# SL_Config_2E.net
KiCad netlist of a schematic drawn in Altium Designer
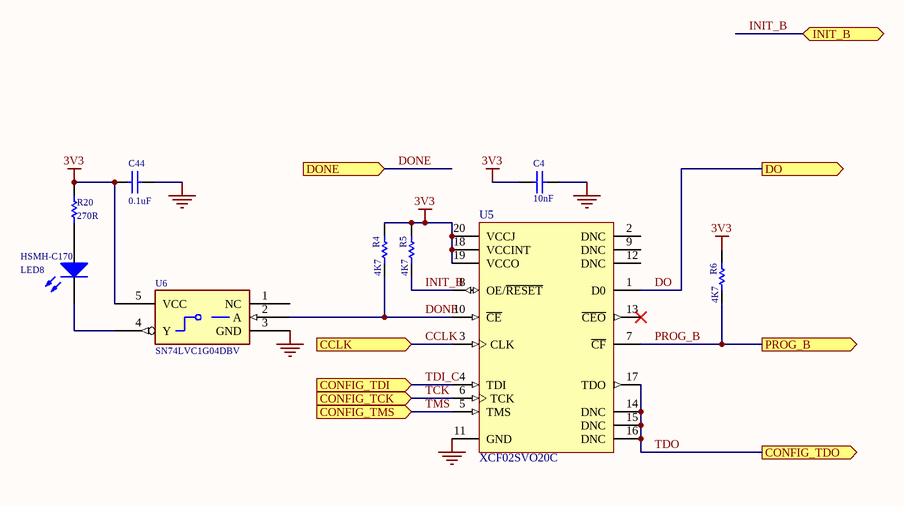
[diagram p0: SL_Config_2E.SchDoc]

(export (version "E")
  (design (tool "Eeschema 10.0.6"))
  (components
    (comp (ref "C4")
      (value "10nF")
      (footprint "CC1608-0603")
      (description "Capacitor")
      (libsource (lib "SpiritLevel_2E") (part "CAP"))
    )
    (comp (ref "C44")
      (value "0.1uF")
      (footprint "CC2012-0805")
      (description "Capacitor")
      (libsource (lib "SpiritLevel_2E") (part "CAP"))
    )
    (comp (ref "LED8")
      (value "HSMH-C170")
      (footprint "Spirit_Level_Project:SMD _LED")
      (description "Typical RED GaAs SMD LED Agilent make")
      (libsource (lib "SpiritLevel_2E") (part "HSMX-C670"))
    )
    (comp (ref "R4")
      (value "4K7")
      (footprint "Spirit_Level_Project:CR2012-0805")
      (description "Resistor")
      (libsource (lib "SpiritLevel_2E") (part "RES"))
    )
    (comp (ref "R5")
      (value "4K7")
      (footprint "Spirit_Level_Project:CR2012-0805")
      (description "Resistor")
      (libsource (lib "SpiritLevel_2E") (part "RES"))
    )
    (comp (ref "R6")
      (value "4K7")
      (footprint "Spirit_Level_Project:CR2012-0805")
      (description "Resistor")
      (libsource (lib "SpiritLevel_2E") (part "RES"))
    )
    (comp (ref "R20")
      (value "270R")
      (footprint "Spirit_Level_Project:CR2012-0805")
      (description "Resistor")
      (libsource (lib "SpiritLevel_2E") (part "RES"))
    )
    (comp (ref "U5")
      (value "XCF02SVO20C")
      (footprint "Spirit_Level_Project:VO20")
      (libsource (lib "SpiritLevel_2E") (part "XCF02SVO20C"))
    )
    (comp (ref "U6")
      (value "SN74LVC1G04DBV")
      (footprint "Spirit_Level_Project:SO-G5/P.95")
      (fields (field (name "MANUFACTURER") "TI"))
      (libsource (lib "SpiritLevel_2E") (part "SN74AHC1G04DBVR"))
    )
  )
  (nets
    (net (code "1") (name "/CCLK") (class "Default")
      (node (ref "U5") (pin "3") (pinfunction "CLK_3") (pintype "input"))
    )
    (net (code "2") (name "/DO") (class "Default")
      (node (ref "U5") (pin "1") (pinfunction "D0_1") (pintype "tri_state"))
    )
    (net (code "3") (name "/DONE") (class "Default")
      (node (ref "R4") (pin "2") (pinfunction "2_2") (pintype "passive"))
      (node (ref "U5") (pin "10") (pinfunction "~{CE}_10") (pintype "input"))
      (node (ref "U6") (pin "2") (pinfunction "A_2") (pintype "input"))
    )
    (net (code "4") (name "/INIT_B") (class "Default")
      (node (ref "R5") (pin "2") (pinfunction "2_2") (pintype "passive"))
      (node (ref "U5") (pin "8") (pinfunction "OE/~{RESET}_8") (pintype "bidirectional"))
    )
    (net (code "5") (name "/PROG_B") (class "Default")
      (node (ref "R6") (pin "2") (pinfunction "2_2") (pintype "passive"))
      (node (ref "U5") (pin "7") (pinfunction "~{CF}_7") (pintype "open_collector"))
    )
    (net (code "6") (name "/TCK") (class "Default")
      (node (ref "U5") (pin "6") (pinfunction "TCK_6") (pintype "input"))
    )
    (net (code "7") (name "/TDI_C") (class "Default")
      (node (ref "U5") (pin "4") (pinfunction "TDI_4") (pintype "input"))
    )
    (net (code "8") (name "/TDO") (class "Default")
      (node (ref "U5") (pin "14") (pinfunction "DNC_14") (pintype "passive"))
      (node (ref "U5") (pin "15") (pinfunction "DNC_15") (pintype "passive"))
      (node (ref "U5") (pin "16") (pinfunction "DNC_16") (pintype "passive"))
      (node (ref "U5") (pin "17") (pinfunction "TDO_17") (pintype "output"))
    )
    (net (code "9") (name "/TMS") (class "Default")
      (node (ref "U5") (pin "5") (pinfunction "TMS_5") (pintype "input"))
    )
    (net (code "10") (name "3V3") (class "Default")
      (node (ref "C4") (pin "1") (pinfunction "1_1") (pintype "passive"))
      (node (ref "C44") (pin "2") (pinfunction "2_2") (pintype "passive"))
      (node (ref "R20") (pin "2") (pinfunction "2_2") (pintype "passive"))
      (node (ref "R4") (pin "1") (pinfunction "1_1") (pintype "passive"))
      (node (ref "R5") (pin "1") (pinfunction "1_1") (pintype "passive"))
      (node (ref "R6") (pin "1") (pinfunction "1_1") (pintype "passive"))
      (node (ref "U5") (pin "18") (pinfunction "VCCINT_18") (pintype "power_in"))
      (node (ref "U5") (pin "19") (pinfunction "VCCO_19") (pintype "power_in"))
      (node (ref "U5") (pin "20") (pinfunction "VCCJ_20") (pintype "power_in"))
      (node (ref "U6") (pin "5") (pinfunction "VCC_5") (pintype "power_in"))
    )
    (net (code "11") (name "GND") (class "Default")
      (node (ref "C4") (pin "2") (pinfunction "2_2") (pintype "passive"))
      (node (ref "C44") (pin "1") (pinfunction "1_1") (pintype "passive"))
      (node (ref "U5") (pin "11") (pinfunction "GND_11") (pintype "power_in"))
      (node (ref "U6") (pin "3") (pinfunction "GND_3") (pintype "power_in"))
    )
    (net (code "12") (name "Net-(LED8-A)") (class "Default")
      (node (ref "LED8") (pin "1") (pinfunction "A_1") (pintype "passive"))
      (node (ref "R20") (pin "1") (pinfunction "1_1") (pintype "passive"))
    )
    (net (code "13") (name "Net-(LED8-K)") (class "Default")
      (node (ref "LED8") (pin "2") (pinfunction "K_2") (pintype "passive"))
      (node (ref "U6") (pin "4") (pinfunction "Y_4") (pintype "output"))
    )
    (net (code "14") (name "unconnected-(U5-DNC-Pad2)") (class "Default")
      (node (ref "U5") (pin "2") (pinfunction "DNC_2") (pintype "passive"))
    )
    (net (code "15") (name "unconnected-(U5-DNC-Pad9)") (class "Default")
      (node (ref "U5") (pin "9") (pinfunction "DNC_9") (pintype "passive"))
    )
    (net (code "16") (name "unconnected-(U5-DNC-Pad12)") (class "Default")
      (node (ref "U5") (pin "12") (pinfunction "DNC_12") (pintype "passive"))
    )
    (net (code "17") (name "unconnected-(U5-~{CEO}-Pad13)") (class "Default")
      (node (ref "U5") (pin "13") (pinfunction "~{CEO}_13") (pintype "output+no_connect"))
    )
    (net (code "18") (name "unconnected-(U6-NC-Pad1)") (class "Default")
      (node (ref "U6") (pin "1") (pinfunction "NC_1") (pintype "passive"))
    )
  )
)
